# Sheet2.net
KiCad netlist of a schematic drawn in Altium Designer
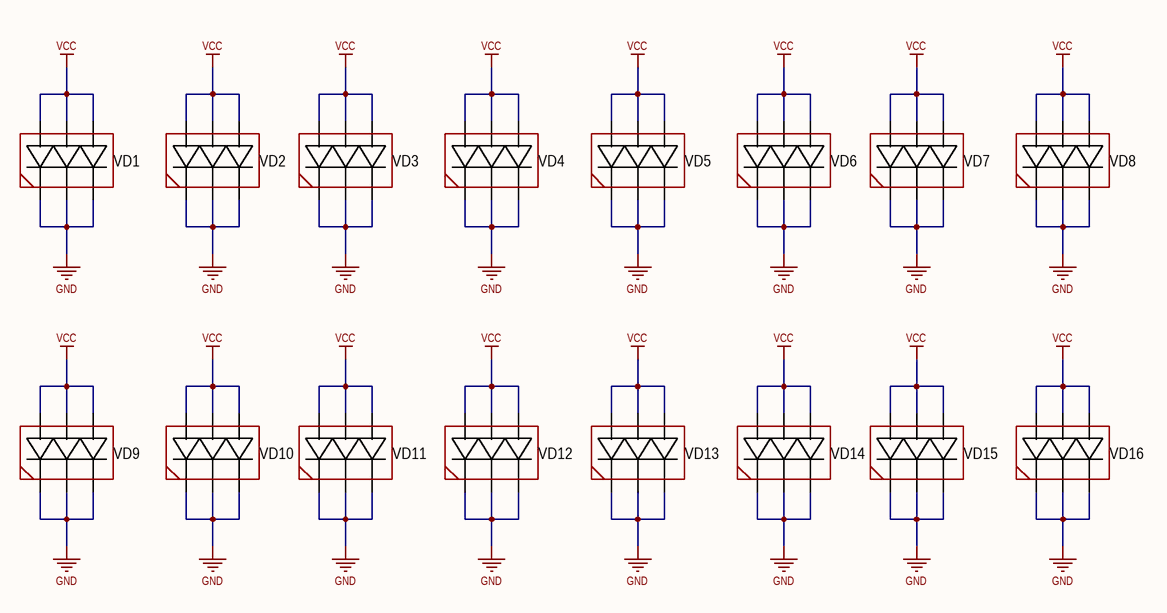
[diagram p0: Sheet2.SchDoc]

(export (version "E")
  (design (tool "Eeschema 10.0.6"))
  (components
    (comp (ref "VD1")
      (value "~")
      (footprint "LED 5050")
      (fields (field (name "VALUEMANUFACTURERPARTNUMBER") "LED, , *, *, *, -55...+150°C"))
      (libsource (lib "diode") (part "LED 5050"))
    )
    (comp (ref "VD2")
      (value "~")
      (footprint "LED 5050")
      (fields (field (name "VALUEMANUFACTURERPARTNUMBER") "LED, , *, *, *, -55...+150°C"))
      (libsource (lib "diode") (part "LED 5050"))
    )
    (comp (ref "VD3")
      (value "~")
      (footprint "LED 5050")
      (fields (field (name "VALUEMANUFACTURERPARTNUMBER") "LED, , *, *, *, -55...+150°C"))
      (libsource (lib "diode") (part "LED 5050"))
    )
    (comp (ref "VD4")
      (value "~")
      (footprint "LED 5050")
      (fields (field (name "VALUEMANUFACTURERPARTNUMBER") "LED, , *, *, *, -55...+150°C"))
      (libsource (lib "diode") (part "LED 5050"))
    )
    (comp (ref "VD5")
      (value "~")
      (footprint "LED 5050")
      (fields (field (name "VALUEMANUFACTURERPARTNUMBER") "LED, , *, *, *, -55...+150°C"))
      (libsource (lib "diode") (part "LED 5050"))
    )
    (comp (ref "VD6")
      (value "~")
      (footprint "LED 5050")
      (fields (field (name "VALUEMANUFACTURERPARTNUMBER") "LED, , *, *, *, -55...+150°C"))
      (libsource (lib "diode") (part "LED 5050"))
    )
    (comp (ref "VD7")
      (value "~")
      (footprint "LED 5050")
      (fields (field (name "VALUEMANUFACTURERPARTNUMBER") "LED, , *, *, *, -55...+150°C"))
      (libsource (lib "diode") (part "LED 5050"))
    )
    (comp (ref "VD8")
      (value "~")
      (footprint "LED 5050")
      (fields (field (name "VALUEMANUFACTURERPARTNUMBER") "LED, , *, *, *, -55...+150°C"))
      (libsource (lib "diode") (part "LED 5050"))
    )
    (comp (ref "VD9")
      (value "~")
      (footprint "LED 5050")
      (fields (field (name "VALUEMANUFACTURERPARTNUMBER") "LED, , *, *, *, -55...+150°C"))
      (libsource (lib "diode") (part "LED 5050"))
    )
    (comp (ref "VD10")
      (value "~")
      (footprint "LED 5050")
      (fields (field (name "VALUEMANUFACTURERPARTNUMBER") "LED, , *, *, *, -55...+150°C"))
      (libsource (lib "diode") (part "LED 5050"))
    )
    (comp (ref "VD11")
      (value "~")
      (footprint "LED 5050")
      (fields (field (name "VALUEMANUFACTURERPARTNUMBER") "LED, , *, *, *, -55...+150°C"))
      (libsource (lib "diode") (part "LED 5050"))
    )
    (comp (ref "VD12")
      (value "~")
      (footprint "LED 5050")
      (fields (field (name "VALUEMANUFACTURERPARTNUMBER") "LED, , *, *, *, -55...+150°C"))
      (libsource (lib "diode") (part "LED 5050"))
    )
    (comp (ref "VD13")
      (value "~")
      (footprint "LED 5050")
      (fields (field (name "VALUEMANUFACTURERPARTNUMBER") "LED, , *, *, *, -55...+150°C"))
      (libsource (lib "diode") (part "LED 5050"))
    )
    (comp (ref "VD14")
      (value "~")
      (footprint "LED 5050")
      (fields (field (name "VALUEMANUFACTURERPARTNUMBER") "LED, , *, *, *, -55...+150°C"))
      (libsource (lib "diode") (part "LED 5050"))
    )
    (comp (ref "VD15")
      (value "~")
      (footprint "LED 5050")
      (fields (field (name "VALUEMANUFACTURERPARTNUMBER") "LED, , *, *, *, -55...+150°C"))
      (libsource (lib "diode") (part "LED 5050"))
    )
    (comp (ref "VD16")
      (value "~")
      (footprint "LED 5050")
      (fields (field (name "VALUEMANUFACTURERPARTNUMBER") "LED, , *, *, *, -55...+150°C"))
      (libsource (lib "diode") (part "LED 5050"))
    )
  )
  (nets
    (net (code "1") (name "GND") (class "Default")
      (node (ref "VD1") (pin "1") (pintype "passive"))
      (node (ref "VD1") (pin "3") (pintype "passive"))
      (node (ref "VD1") (pin "5") (pintype "passive"))
      (node (ref "VD10") (pin "1") (pintype "passive"))
      (node (ref "VD10") (pin "3") (pintype "passive"))
      (node (ref "VD10") (pin "5") (pintype "passive"))
      (node (ref "VD11") (pin "1") (pintype "passive"))
      (node (ref "VD11") (pin "3") (pintype "passive"))
      (node (ref "VD11") (pin "5") (pintype "passive"))
      (node (ref "VD12") (pin "1") (pintype "passive"))
      (node (ref "VD12") (pin "3") (pintype "passive"))
      (node (ref "VD12") (pin "5") (pintype "passive"))
      (node (ref "VD13") (pin "1") (pintype "passive"))
      (node (ref "VD13") (pin "3") (pintype "passive"))
      (node (ref "VD13") (pin "5") (pintype "passive"))
      (node (ref "VD14") (pin "1") (pintype "passive"))
      (node (ref "VD14") (pin "3") (pintype "passive"))
      (node (ref "VD14") (pin "5") (pintype "passive"))
      (node (ref "VD15") (pin "1") (pintype "passive"))
      (node (ref "VD15") (pin "3") (pintype "passive"))
      (node (ref "VD15") (pin "5") (pintype "passive"))
      (node (ref "VD16") (pin "1") (pintype "passive"))
      (node (ref "VD16") (pin "3") (pintype "passive"))
      (node (ref "VD16") (pin "5") (pintype "passive"))
      (node (ref "VD2") (pin "1") (pintype "passive"))
      (node (ref "VD2") (pin "3") (pintype "passive"))
      (node (ref "VD2") (pin "5") (pintype "passive"))
      (node (ref "VD3") (pin "1") (pintype "passive"))
      (node (ref "VD3") (pin "3") (pintype "passive"))
      (node (ref "VD3") (pin "5") (pintype "passive"))
      (node (ref "VD4") (pin "1") (pintype "passive"))
      (node (ref "VD4") (pin "3") (pintype "passive"))
      (node (ref "VD4") (pin "5") (pintype "passive"))
      (node (ref "VD5") (pin "1") (pintype "passive"))
      (node (ref "VD5") (pin "3") (pintype "passive"))
      (node (ref "VD5") (pin "5") (pintype "passive"))
      (node (ref "VD6") (pin "1") (pintype "passive"))
      (node (ref "VD6") (pin "3") (pintype "passive"))
      (node (ref "VD6") (pin "5") (pintype "passive"))
      (node (ref "VD7") (pin "1") (pintype "passive"))
      (node (ref "VD7") (pin "3") (pintype "passive"))
      (node (ref "VD7") (pin "5") (pintype "passive"))
      (node (ref "VD8") (pin "1") (pintype "passive"))
      (node (ref "VD8") (pin "3") (pintype "passive"))
      (node (ref "VD8") (pin "5") (pintype "passive"))
      (node (ref "VD9") (pin "1") (pintype "passive"))
      (node (ref "VD9") (pin "3") (pintype "passive"))
      (node (ref "VD9") (pin "5") (pintype "passive"))
    )
    (net (code "2") (name "VCC") (class "Default")
      (node (ref "VD1") (pin "2") (pintype "passive"))
      (node (ref "VD1") (pin "4") (pintype "passive"))
      (node (ref "VD1") (pin "6") (pintype "passive"))
      (node (ref "VD10") (pin "2") (pintype "passive"))
      (node (ref "VD10") (pin "4") (pintype "passive"))
      (node (ref "VD10") (pin "6") (pintype "passive"))
      (node (ref "VD11") (pin "2") (pintype "passive"))
      (node (ref "VD11") (pin "4") (pintype "passive"))
      (node (ref "VD11") (pin "6") (pintype "passive"))
      (node (ref "VD12") (pin "2") (pintype "passive"))
      (node (ref "VD12") (pin "4") (pintype "passive"))
      (node (ref "VD12") (pin "6") (pintype "passive"))
      (node (ref "VD13") (pin "2") (pintype "passive"))
      (node (ref "VD13") (pin "4") (pintype "passive"))
      (node (ref "VD13") (pin "6") (pintype "passive"))
      (node (ref "VD14") (pin "2") (pintype "passive"))
      (node (ref "VD14") (pin "4") (pintype "passive"))
      (node (ref "VD14") (pin "6") (pintype "passive"))
      (node (ref "VD15") (pin "2") (pintype "passive"))
      (node (ref "VD15") (pin "4") (pintype "passive"))
      (node (ref "VD15") (pin "6") (pintype "passive"))
      (node (ref "VD16") (pin "2") (pintype "passive"))
      (node (ref "VD16") (pin "4") (pintype "passive"))
      (node (ref "VD16") (pin "6") (pintype "passive"))
      (node (ref "VD2") (pin "2") (pintype "passive"))
      (node (ref "VD2") (pin "4") (pintype "passive"))
      (node (ref "VD2") (pin "6") (pintype "passive"))
      (node (ref "VD3") (pin "2") (pintype "passive"))
      (node (ref "VD3") (pin "4") (pintype "passive"))
      (node (ref "VD3") (pin "6") (pintype "passive"))
      (node (ref "VD4") (pin "2") (pintype "passive"))
      (node (ref "VD4") (pin "4") (pintype "passive"))
      (node (ref "VD4") (pin "6") (pintype "passive"))
      (node (ref "VD5") (pin "2") (pintype "passive"))
      (node (ref "VD5") (pin "4") (pintype "passive"))
      (node (ref "VD5") (pin "6") (pintype "passive"))
      (node (ref "VD6") (pin "2") (pintype "passive"))
      (node (ref "VD6") (pin "4") (pintype "passive"))
      (node (ref "VD6") (pin "6") (pintype "passive"))
      (node (ref "VD7") (pin "2") (pintype "passive"))
      (node (ref "VD7") (pin "4") (pintype "passive"))
      (node (ref "VD7") (pin "6") (pintype "passive"))
      (node (ref "VD8") (pin "2") (pintype "passive"))
      (node (ref "VD8") (pin "4") (pintype "passive"))
      (node (ref "VD8") (pin "6") (pintype "passive"))
      (node (ref "VD9") (pin "2") (pintype "passive"))
      (node (ref "VD9") (pin "4") (pintype "passive"))
      (node (ref "VD9") (pin "6") (pintype "passive"))
    )
  )
)
